# STM_MCU.net
KiCad netlist of a schematic drawn in Altium Designer
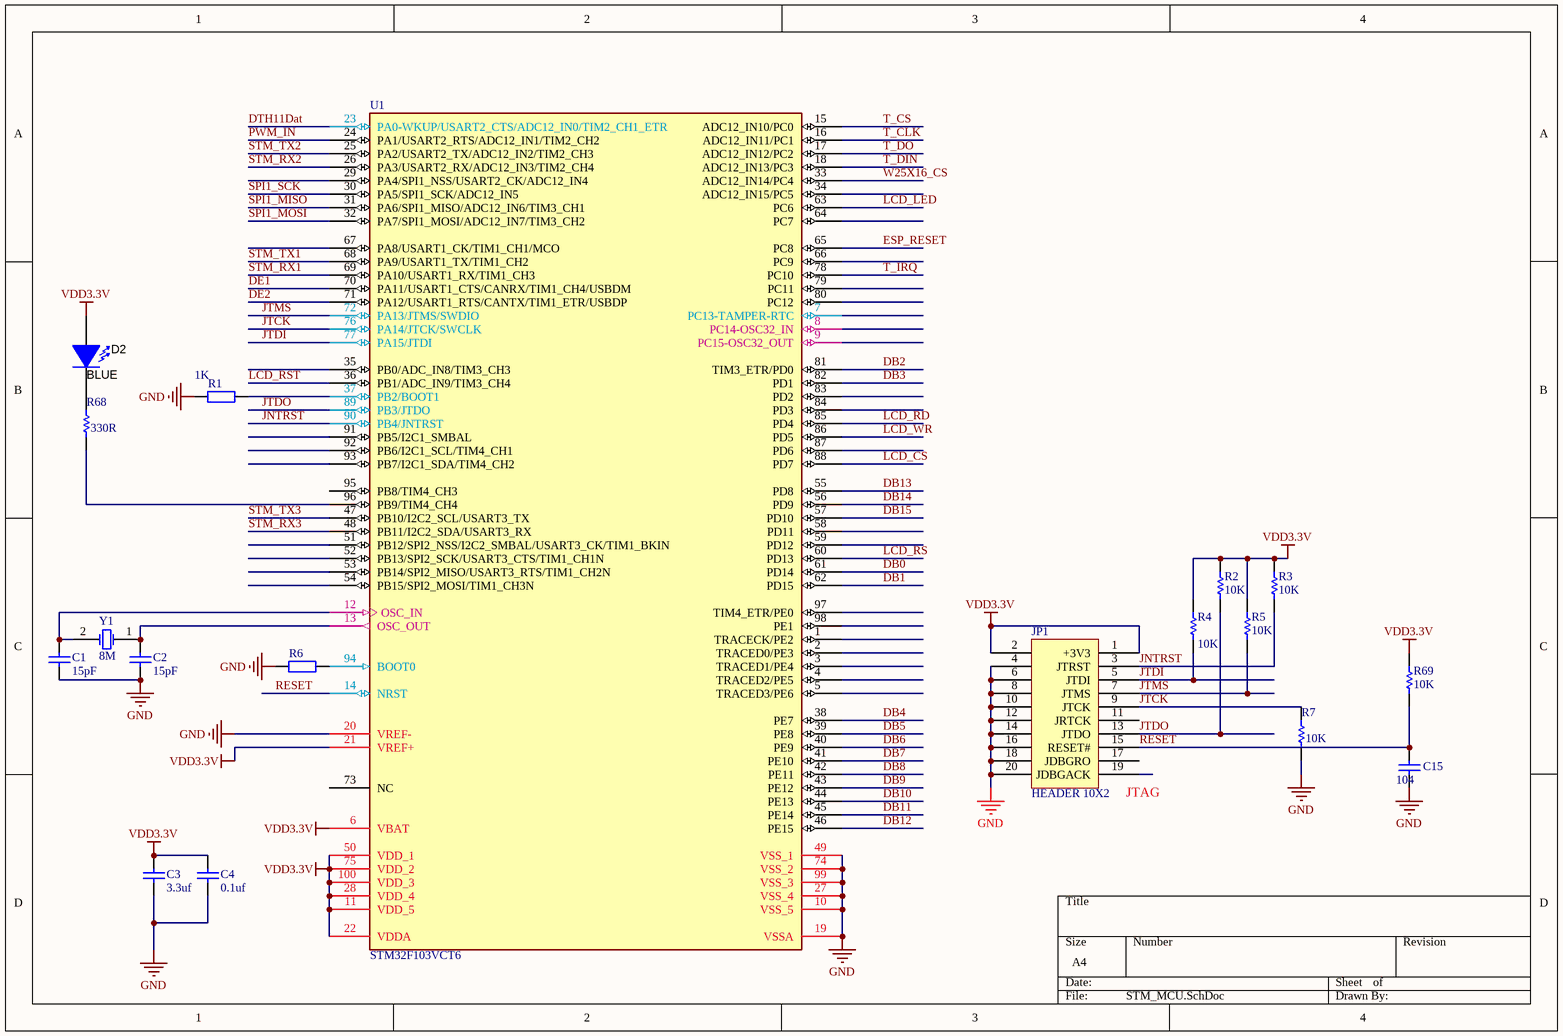
[diagram p0: STM_MCU.SchDoc]

(export (version "E")
  (design (tool "Eeschema 10.0.6"))
  (components
    (comp (ref "C1")
      (value "15pF")
      (footprint "C0805")
      (description "Capacitor")
      (fields (field (name "Comment") "Cap") (field (name "PUBLISHER") "Altium Limited"))
      (libsource (lib "Miscellaneous Devices") (part "Cap"))
    )
    (comp (ref "C2")
      (value "15pF")
      (footprint "C0805")
      (description "Capacitor")
      (fields (field (name "Comment") "Cap") (field (name "PUBLISHER") "Altium Limited"))
      (libsource (lib "Miscellaneous Devices") (part "Cap"))
    )
    (comp (ref "C3")
      (value "3.3uf")
      (footprint "C0805")
      (description "Capacitor")
      (fields
        (field (name "MANUFACTURER") "Generic Components")
        (field (name "Comment") "Cap")
        (field (name "PUBLISHER") "Altium Hobart Technology Centre")
      )
      (libsource (lib "Miscellaneous Devices") (part "Cap"))
    )
    (comp (ref "C4")
      (value "0.1uf")
      (footprint "C0805")
      (description "Capacitor")
      (fields
        (field (name "MANUFACTURER") "Generic Components")
        (field (name "Comment") "Cap")
        (field (name "PUBLISHER") "Altium Hobart Technology Centre")
      )
      (libsource (lib "Miscellaneous Devices") (part "Cap"))
    )
    (comp (ref "C15")
      (value "104")
      (footprint "C0805")
      (description "Capacitor")
      (fields (field (name "PUBLISHER") "Altium Limited"))
      (libsource (lib "main board") (part "Cap_2"))
    )
    (comp (ref "D2")
      (value "BLUE")
      (footprint "D0805")
      (description "LED, GREEN SMD")
      (fields
        (field (name "MANUFACTURER") "Rohm")
        (field (name "PARTNUMBER") "SML-P12YTT86")
        (field (name "PUBLISHER") "Texas Instruments")
      )
      (libsource (lib "REl") (part "SML-P12YTT86"))
    )
    (comp (ref "JP1")
      (value "HEADER 10X2")
      (footprint "STM32-JLINK")
      (libsource (lib "*") (part "HEADER 10X2"))
    )
    (comp (ref "R1")
      (value "1K")
      (footprint "0805")
      (fields (field (name "Comment") "Res2"))
      (libsource (lib "S1") (part "RES"))
    )
    (comp (ref "R2")
      (value "10K")
      (footprint "0805")
      (description "Semiconductor Resistor")
      (fields (field (name "Comment") "Res Semi") (field (name "PUBLISHER") "Altium Limited"))
      (libsource (lib "Miscellaneous Devices") (part "Res Semi"))
    )
    (comp (ref "R3")
      (value "10K")
      (footprint "0805")
      (description "Semiconductor Resistor")
      (fields (field (name "Comment") "Res Semi") (field (name "PUBLISHER") "Altium Limited"))
      (libsource (lib "Miscellaneous Devices") (part "Res Semi"))
    )
    (comp (ref "R4")
      (value "10K")
      (footprint "0805")
      (description "Semiconductor Resistor")
      (fields (field (name "Comment") "Res Semi") (field (name "PUBLISHER") "Altium Limited"))
      (libsource (lib "Miscellaneous Devices") (part "Res Semi"))
    )
    (comp (ref "R5")
      (value "10K")
      (footprint "0805")
      (description "Semiconductor Resistor")
      (fields (field (name "Comment") "Res Semi") (field (name "PUBLISHER") "Altium Limited"))
      (libsource (lib "Miscellaneous Devices") (part "Res Semi"))
    )
    (comp (ref "R6") (value "Res2") (footprint "0805") (libsource (lib "S1") (part "RES")))
    (comp (ref "R7")
      (value "10K")
      (footprint "0805")
      (description "Semiconductor Resistor")
      (fields (field (name "Comment") "Res Semi") (field (name "PUBLISHER") "Altium Limited"))
      (libsource (lib "Miscellaneous Devices") (part "Res Semi"))
    )
    (comp (ref "R68")
      (value "330R")
      (footprint "0805")
      (description "Semiconductor Resistor")
      (fields (field (name "Comment") "Res Semi") (field (name "PUBLISHER") "Altium Limited"))
      (libsource (lib "Miscellaneous Devices") (part "Res Semi"))
    )
    (comp (ref "R69")
      (value "10K")
      (footprint "0805")
      (description "Semiconductor Resistor")
      (fields (field (name "PUBLISHER") "Altium Limited"))
      (libsource (lib "Miscellaneous Devices") (part "Res Semi"))
    )
    (comp (ref "U1")
      (value "STM32F103VCT6")
      (footprint "LQFP100_M")
      (description "STM32 ARM-based 32-bit MCU with 64 Kbytes Flash, 100-pin LQFP, Industrial Temperature")
      (fields (field (name "PUBLISHER") "*"))
      (libsource (lib "Microcontroller Unit") (part "STM32F103VBT6"))
    )
    (comp (ref "Y1")
      (value "XTAL")
      (footprint "CY")
      (description "Crystal Oscillator")
      (fields (field (name "ALTIUM_UNNAMED_1") "8M") (field (name "PUBLISHER") "Altium Limited"))
      (libsource (lib "Miscellaneous Devices") (part "XTAL"))
    )
  )
  (nets
    (net (code "1") (name "/DB0") (class "Default")
      (node (ref "U1") (pin "61") (pinfunction "PD14_61") (pintype "bidirectional"))
    )
    (net (code "2") (name "/DB1") (class "Default")
      (node (ref "U1") (pin "62") (pinfunction "PD15_62") (pintype "bidirectional"))
    )
    (net (code "3") (name "/DB2") (class "Default")
      (node (ref "U1") (pin "81") (pinfunction "TIM3_ETR/PD0_81") (pintype "bidirectional"))
    )
    (net (code "4") (name "/DB3") (class "Default")
      (node (ref "U1") (pin "82") (pinfunction "PD1_82") (pintype "bidirectional"))
    )
    (net (code "5") (name "/DB4") (class "Default")
      (node (ref "U1") (pin "38") (pinfunction "PE7_38") (pintype "bidirectional"))
    )
    (net (code "6") (name "/DB5") (class "Default")
      (node (ref "U1") (pin "39") (pinfunction "PE8_39") (pintype "bidirectional"))
    )
    (net (code "7") (name "/DB6") (class "Default")
      (node (ref "U1") (pin "40") (pinfunction "PE9_40") (pintype "bidirectional"))
    )
    (net (code "8") (name "/DB7") (class "Default")
      (node (ref "U1") (pin "41") (pinfunction "PE10_41") (pintype "bidirectional"))
    )
    (net (code "9") (name "/DB8") (class "Default")
      (node (ref "U1") (pin "42") (pinfunction "PE11_42") (pintype "bidirectional"))
    )
    (net (code "10") (name "/DB9") (class "Default")
      (node (ref "U1") (pin "43") (pinfunction "PE12_43") (pintype "bidirectional"))
    )
    (net (code "11") (name "/DB10") (class "Default")
      (node (ref "U1") (pin "44") (pinfunction "PE13_44") (pintype "bidirectional"))
    )
    (net (code "12") (name "/DB11") (class "Default")
      (node (ref "U1") (pin "45") (pinfunction "PE14_45") (pintype "bidirectional"))
    )
    (net (code "13") (name "/DB12") (class "Default")
      (node (ref "U1") (pin "46") (pinfunction "PE15_46") (pintype "bidirectional"))
    )
    (net (code "14") (name "/DB13") (class "Default")
      (node (ref "U1") (pin "55") (pinfunction "PD8_55") (pintype "bidirectional"))
    )
    (net (code "15") (name "/DB14") (class "Default")
      (node (ref "U1") (pin "56") (pinfunction "PD9_56") (pintype "bidirectional"))
    )
    (net (code "16") (name "/DB15") (class "Default")
      (node (ref "U1") (pin "57") (pinfunction "PD10_57") (pintype "bidirectional"))
    )
    (net (code "17") (name "/DE1") (class "Default")
      (node (ref "U1") (pin "70") (pinfunction "PA11/USART1_CTS/CANRX/TIM1_CH4/USBDM_70") (pintype "bidirectional"))
    )
    (net (code "18") (name "/DE2") (class "Default")
      (node (ref "U1") (pin "71") (pinfunction "PA12/USART1_RTS/CANTX/TIM1_ETR/USBDP_71") (pintype "bidirectional"))
    )
    (net (code "19") (name "/DTH11Dat") (class "Default")
      (node (ref "U1") (pin "23") (pinfunction "PA0-WKUP/USART2_CTS/ADC12_IN0/TIM2_CH1_ETR_23") (pintype "bidirectional"))
    )
    (net (code "20") (name "/ESP_RESET") (class "Default")
      (node (ref "U1") (pin "65") (pinfunction "PC8_65") (pintype "bidirectional"))
    )
    (net (code "21") (name "/JNTRST") (class "Default")
      (node (ref "JP1") (pin "3") (pinfunction "JTRST_3") (pintype "passive"))
      (node (ref "R3") (pin "1") (pinfunction "1_1") (pintype "passive"))
      (node (ref "U1") (pin "90") (pinfunction "PB4/JNTRST_90") (pintype "bidirectional"))
    )
    (net (code "22") (name "/JTCK") (class "Default")
      (node (ref "JP1") (pin "9") (pinfunction "JTCK_9") (pintype "passive"))
      (node (ref "R7") (pin "2") (pinfunction "2_2") (pintype "passive"))
      (node (ref "U1") (pin "76") (pinfunction "PA14/JTCK/SWCLK_76") (pintype "bidirectional"))
    )
    (net (code "23") (name "/JTDI") (class "Default")
      (node (ref "JP1") (pin "5") (pinfunction "JTDI_5") (pintype "passive"))
      (node (ref "R4") (pin "1") (pinfunction "1_1") (pintype "passive"))
      (node (ref "U1") (pin "77") (pinfunction "PA15/JTDI_77") (pintype "bidirectional"))
    )
    (net (code "24") (name "/JTDO") (class "Default")
      (node (ref "JP1") (pin "13") (pinfunction "JTDO_13") (pintype "passive"))
      (node (ref "R2") (pin "1") (pinfunction "1_1") (pintype "passive"))
      (node (ref "U1") (pin "89") (pinfunction "PB3/JTDO_89") (pintype "bidirectional"))
    )
    (net (code "25") (name "/JTMS") (class "Default")
      (node (ref "JP1") (pin "7") (pinfunction "JTMS_7") (pintype "passive"))
      (node (ref "R5") (pin "1") (pinfunction "1_1") (pintype "passive"))
      (node (ref "U1") (pin "72") (pinfunction "PA13/JTMS/SWDIO_72") (pintype "bidirectional"))
    )
    (net (code "26") (name "/LCD_CS") (class "Default")
      (node (ref "U1") (pin "88") (pinfunction "PD7_88") (pintype "bidirectional"))
    )
    (net (code "27") (name "/LCD_LED") (class "Default")
      (node (ref "U1") (pin "63") (pinfunction "PC6_63") (pintype "bidirectional"))
    )
    (net (code "28") (name "/LCD_RD") (class "Default")
      (node (ref "U1") (pin "85") (pinfunction "PD4_85") (pintype "bidirectional"))
    )
    (net (code "29") (name "/LCD_RS") (class "Default")
      (node (ref "U1") (pin "60") (pinfunction "PD13_60") (pintype "bidirectional"))
    )
    (net (code "30") (name "/LCD_RST") (class "Default")
      (node (ref "U1") (pin "36") (pinfunction "PB1/ADC_IN9/TIM3_CH4_36") (pintype "bidirectional"))
    )
    (net (code "31") (name "/LCD_WR") (class "Default")
      (node (ref "U1") (pin "86") (pinfunction "PD5_86") (pintype "bidirectional"))
    )
    (net (code "32") (name "/PWM_IN") (class "Default")
      (node (ref "U1") (pin "24") (pinfunction "PA1/USART2_RTS/ADC12_IN1/TIM2_CH2_24") (pintype "bidirectional"))
    )
    (net (code "33") (name "/RESET") (class "Default")
      (node (ref "C15") (pin "2") (pinfunction "2_2") (pintype "passive"))
      (node (ref "JP1") (pin "15") (pinfunction "RESET#_15") (pintype "passive"))
      (node (ref "R69") (pin "1") (pinfunction "1_1") (pintype "passive"))
      (node (ref "U1") (pin "14") (pinfunction "NRST_14") (pintype "bidirectional"))
    )
    (net (code "34") (name "/SPI1_MISO") (class "Default")
      (node (ref "U1") (pin "31") (pinfunction "PA6/SPI1_MISO/ADC12_IN6/TIM3_CH1_31") (pintype "bidirectional"))
    )
    (net (code "35") (name "/SPI1_MOSI") (class "Default")
      (node (ref "U1") (pin "32") (pinfunction "PA7/SPI1_MOSI/ADC12_IN7/TIM3_CH2_32") (pintype "bidirectional"))
    )
    (net (code "36") (name "/SPI1_SCK") (class "Default")
      (node (ref "U1") (pin "30") (pinfunction "PA5/SPI1_SCK/ADC12_IN5_30") (pintype "bidirectional"))
    )
    (net (code "37") (name "/STM_RX1") (class "Default")
      (node (ref "U1") (pin "69") (pinfunction "PA10/USART1_RX/TIM1_CH3_69") (pintype "bidirectional"))
    )
    (net (code "38") (name "/STM_RX2") (class "Default")
      (node (ref "U1") (pin "26") (pinfunction "PA3/USART2_RX/ADC12_IN3/TIM2_CH4_26") (pintype "bidirectional"))
    )
    (net (code "39") (name "/STM_RX3") (class "Default")
      (node (ref "U1") (pin "48") (pinfunction "PB11/I2C2_SDA/USART3_RX_48") (pintype "bidirectional"))
    )
    (net (code "40") (name "/STM_TX1") (class "Default")
      (node (ref "U1") (pin "68") (pinfunction "PA9/USART1_TX/TIM1_CH2_68") (pintype "bidirectional"))
    )
    (net (code "41") (name "/STM_TX2") (class "Default")
      (node (ref "U1") (pin "25") (pinfunction "PA2/USART2_TX/ADC12_IN2/TIM2_CH3_25") (pintype "bidirectional"))
    )
    (net (code "42") (name "/STM_TX3") (class "Default")
      (node (ref "U1") (pin "47") (pinfunction "PB10/I2C2_SCL/USART3_TX_47") (pintype "bidirectional"))
    )
    (net (code "43") (name "/T_CLK") (class "Default")
      (node (ref "U1") (pin "16") (pinfunction "ADC12_IN11/PC1_16") (pintype "bidirectional"))
    )
    (net (code "44") (name "/T_CS") (class "Default")
      (node (ref "U1") (pin "15") (pinfunction "ADC12_IN10/PC0_15") (pintype "bidirectional"))
    )
    (net (code "45") (name "/T_DIN") (class "Default")
      (node (ref "U1") (pin "18") (pinfunction "ADC12_IN13/PC3_18") (pintype "bidirectional"))
    )
    (net (code "46") (name "/T_DO") (class "Default")
      (node (ref "U1") (pin "17") (pinfunction "ADC12_IN12/PC2_17") (pintype "bidirectional"))
    )
    (net (code "47") (name "/T_IRQ") (class "Default")
      (node (ref "U1") (pin "78") (pinfunction "PC10_78") (pintype "bidirectional"))
    )
    (net (code "48") (name "/W25X16_CS") (class "Default")
      (node (ref "U1") (pin "33") (pinfunction "ADC12_IN14/PC4_33") (pintype "bidirectional"))
    )
    (net (code "49") (name "GND") (class "Default")
      (node (ref "C1") (pin "1") (pinfunction "1_1") (pintype "passive"))
      (node (ref "C15") (pin "1") (pinfunction "1_1") (pintype "passive"))
      (node (ref "C2") (pin "1") (pinfunction "1_1") (pintype "passive"))
      (node (ref "C3") (pin "2") (pinfunction "2_2") (pintype "passive"))
      (node (ref "C4") (pin "2") (pinfunction "2_2") (pintype "passive"))
      (node (ref "JP1") (pin "10") (pintype "passive"))
      (node (ref "JP1") (pin "12") (pintype "passive"))
      (node (ref "JP1") (pin "14") (pintype "passive"))
      (node (ref "JP1") (pin "16") (pintype "passive"))
      (node (ref "JP1") (pin "18") (pintype "passive"))
      (node (ref "JP1") (pin "20") (pintype "passive"))
      (node (ref "JP1") (pin "4") (pintype "passive"))
      (node (ref "JP1") (pin "6") (pintype "passive"))
      (node (ref "JP1") (pin "8") (pintype "passive"))
      (node (ref "R1") (pin "1") (pinfunction "1_1") (pintype "passive"))
      (node (ref "R6") (pin "1") (pinfunction "1_1") (pintype "passive"))
      (node (ref "R7") (pin "1") (pinfunction "1_1") (pintype "passive"))
      (node (ref "U1") (pin "10") (pinfunction "VSS_5_10") (pintype "power_in"))
      (node (ref "U1") (pin "19") (pinfunction "VSSA_19") (pintype "power_in"))
      (node (ref "U1") (pin "20") (pinfunction "VREF-_20") (pintype "power_in"))
      (node (ref "U1") (pin "27") (pinfunction "VSS_4_27") (pintype "power_in"))
      (node (ref "U1") (pin "49") (pinfunction "VSS_1_49") (pintype "power_in"))
      (node (ref "U1") (pin "74") (pinfunction "VSS_2_74") (pintype "power_in"))
      (node (ref "U1") (pin "99") (pinfunction "VSS_3_99") (pintype "power_in"))
    )
    (net (code "50") (name "Net-(D2-K)") (class "Default")
      (node (ref "D2") (pin "2") (pinfunction "K_2") (pintype "passive"))
      (node (ref "R68") (pin "2") (pinfunction "2_2") (pintype "passive"))
    )
    (net (code "51") (name "Net-(U1-BOOT0)") (class "Default")
      (node (ref "R6") (pin "2") (pinfunction "2_2") (pintype "passive"))
      (node (ref "U1") (pin "94") (pinfunction "BOOT0_94") (pintype "input"))
    )
    (net (code "52") (name "Net-(U1-OSC_IN)") (class "Default")
      (node (ref "C1") (pin "2") (pinfunction "2_2") (pintype "passive"))
      (node (ref "U1") (pin "12") (pinfunction "OSC_IN_12") (pintype "input"))
      (node (ref "Y1") (pin "2") (pinfunction "OSC2_2") (pintype "passive"))
    )
    (net (code "53") (name "Net-(U1-OSC_OUT)") (class "Default")
      (node (ref "C2") (pin "2") (pinfunction "2_2") (pintype "passive"))
      (node (ref "U1") (pin "13") (pinfunction "OSC_OUT_13") (pintype "output"))
      (node (ref "Y1") (pin "1") (pinfunction "OSC1_1") (pintype "passive"))
    )
    (net (code "54") (name "Net-(U1-PB2{slash}BOOT1)") (class "Default")
      (node (ref "R1") (pin "2") (pinfunction "2_2") (pintype "passive"))
      (node (ref "U1") (pin "37") (pinfunction "PB2/BOOT1_37") (pintype "bidirectional"))
    )
    (net (code "55") (name "Net-(U1-PB9{slash}TIM4_CH4)") (class "Default")
      (node (ref "R68") (pin "1") (pinfunction "1_1") (pintype "passive"))
      (node (ref "U1") (pin "96") (pinfunction "PB9/TIM4_CH4_96") (pintype "bidirectional"))
    )
    (net (code "56") (name "VDD3.3V") (class "Default")
      (node (ref "C3") (pin "1") (pinfunction "1_1") (pintype "passive"))
      (node (ref "C4") (pin "1") (pinfunction "1_1") (pintype "passive"))
      (node (ref "D2") (pin "1") (pinfunction "A_1") (pintype "passive"))
      (node (ref "JP1") (pin "1") (pinfunction "+3V3_1") (pintype "passive"))
      (node (ref "JP1") (pin "2") (pintype "passive"))
      (node (ref "R2") (pin "2") (pinfunction "2_2") (pintype "passive"))
      (node (ref "R3") (pin "2") (pinfunction "2_2") (pintype "passive"))
      (node (ref "R4") (pin "2") (pinfunction "2_2") (pintype "passive"))
      (node (ref "R5") (pin "2") (pinfunction "2_2") (pintype "passive"))
      (node (ref "R69") (pin "2") (pinfunction "2_2") (pintype "passive"))
      (node (ref "U1") (pin "100") (pinfunction "VDD_3_100") (pintype "power_in"))
      (node (ref "U1") (pin "11") (pinfunction "VDD_5_11") (pintype "power_in"))
      (node (ref "U1") (pin "21") (pinfunction "VREF+_21") (pintype "power_in"))
      (node (ref "U1") (pin "22") (pinfunction "VDDA_22") (pintype "power_in"))
      (node (ref "U1") (pin "28") (pinfunction "VDD_4_28") (pintype "power_in"))
      (node (ref "U1") (pin "50") (pinfunction "VDD_1_50") (pintype "power_in"))
      (node (ref "U1") (pin "6") (pinfunction "VBAT_6") (pintype "power_in"))
      (node (ref "U1") (pin "75") (pinfunction "VDD_2_75") (pintype "power_in"))
    )
    (net (code "57") (name "unconnected-(JP1-JDBGACK-Pad19)") (class "Default")
      (node (ref "JP1") (pin "19") (pinfunction "JDBGACK_19") (pintype "passive"))
    )
    (net (code "58") (name "unconnected-(JP1-JDBGRO-Pad17)") (class "Default")
      (node (ref "JP1") (pin "17") (pinfunction "JDBGRO_17") (pintype "passive"))
    )
    (net (code "59") (name "unconnected-(JP1-JRTCK-Pad11)") (class "Default")
      (node (ref "JP1") (pin "11") (pinfunction "JRTCK_11") (pintype "passive"))
    )
    (net (code "60") (name "unconnected-(U1-ADC12_IN15{slash}PC5-Pad34)") (class "Default")
      (node (ref "U1") (pin "34") (pinfunction "ADC12_IN15/PC5_34") (pintype "bidirectional"))
    )
    (net (code "61") (name "unconnected-(U1-NC-Pad73)") (class "Default")
      (node (ref "U1") (pin "73") (pinfunction "NC_73") (pintype "tri_state"))
    )
    (net (code "62") (name "unconnected-(U1-PA4{slash}SPI1_NSS{slash}USART2_CK{slash}ADC12_IN4-Pad29)") (class "Default")
      (node (ref "U1") (pin "29") (pinfunction "PA4/SPI1_NSS/USART2_CK/ADC12_IN4_29") (pintype "bidirectional"))
    )
    (net (code "63") (name "unconnected-(U1-PA8{slash}USART1_CK{slash}TIM1_CH1{slash}MCO-Pad67)") (class "Default")
      (node (ref "U1") (pin "67") (pinfunction "PA8/USART1_CK/TIM1_CH1/MCO_67") (pintype "bidirectional"))
    )
    (net (code "64") (name "unconnected-(U1-PB0{slash}ADC_IN8{slash}TIM3_CH3-Pad35)") (class "Default")
      (node (ref "U1") (pin "35") (pinfunction "PB0/ADC_IN8/TIM3_CH3_35") (pintype "bidirectional"))
    )
    (net (code "65") (name "unconnected-(U1-PB5{slash}I2C1_SMBAL-Pad91)") (class "Default")
      (node (ref "U1") (pin "91") (pinfunction "PB5/I2C1_SMBAL_91") (pintype "bidirectional"))
    )
    (net (code "66") (name "unconnected-(U1-PB6{slash}I2C1_SCL{slash}TIM4_CH1-Pad92)") (class "Default")
      (node (ref "U1") (pin "92") (pinfunction "PB6/I2C1_SCL/TIM4_CH1_92") (pintype "bidirectional"))
    )
    (net (code "67") (name "unconnected-(U1-PB7{slash}I2C1_SDA{slash}TIM4_CH2-Pad93)") (class "Default")
      (node (ref "U1") (pin "93") (pinfunction "PB7/I2C1_SDA/TIM4_CH2_93") (pintype "bidirectional"))
    )
    (net (code "68") (name "unconnected-(U1-PB8{slash}TIM4_CH3-Pad95)") (class "Default")
      (node (ref "U1") (pin "95") (pinfunction "PB8/TIM4_CH3_95") (pintype "bidirectional"))
    )
    (net (code "69") (name "unconnected-(U1-PB12{slash}SPI2_NSS{slash}I2C2_SMBAL{slash}USART3_CK{slash}TIM1_BKIN-Pad51)") (class "Default")
      (node (ref "U1") (pin "51") (pinfunction "PB12/SPI2_NSS/I2C2_SMBAL/USART3_CK/TIM1_BKIN_51") (pintype "bidirectional"))
    )
    (net (code "70") (name "unconnected-(U1-PB13{slash}SPI2_SCK{slash}USART3_CTS{slash}TIM1_CH1N-Pad52)") (class "Default")
      (node (ref "U1") (pin "52") (pinfunction "PB13/SPI2_SCK/USART3_CTS/TIM1_CH1N_52") (pintype "bidirectional"))
    )
    (net (code "71") (name "unconnected-(U1-PB14{slash}SPI2_MISO{slash}USART3_RTS{slash}TIM1_CH2N-Pad53)") (class "Default")
      (node (ref "U1") (pin "53") (pinfunction "PB14/SPI2_MISO/USART3_RTS/TIM1_CH2N_53") (pintype "bidirectional"))
    )
    (net (code "72") (name "unconnected-(U1-PB15{slash}SPI2_MOSI{slash}TIM1_CH3N-Pad54)") (class "Default")
      (node (ref "U1") (pin "54") (pinfunction "PB15/SPI2_MOSI/TIM1_CH3N_54") (pintype "bidirectional"))
    )
    (net (code "73") (name "unconnected-(U1-PC7-Pad64)") (class "Default")
      (node (ref "U1") (pin "64") (pinfunction "PC7_64") (pintype "bidirectional"))
    )
    (net (code "74") (name "unconnected-(U1-PC9-Pad66)") (class "Default")
      (node (ref "U1") (pin "66") (pinfunction "PC9_66") (pintype "bidirectional"))
    )
    (net (code "75") (name "unconnected-(U1-PC11-Pad79)") (class "Default")
      (node (ref "U1") (pin "79") (pinfunction "PC11_79") (pintype "bidirectional"))
    )
    (net (code "76") (name "unconnected-(U1-PC12-Pad80)") (class "Default")
      (node (ref "U1") (pin "80") (pinfunction "PC12_80") (pintype "bidirectional"))
    )
    (net (code "77") (name "unconnected-(U1-PC13-TAMPER-RTC-Pad7)") (class "Default")
      (node (ref "U1") (pin "7") (pinfunction "PC13-TAMPER-RTC_7") (pintype "bidirectional"))
    )
    (net (code "78") (name "unconnected-(U1-PC14-OSC32_IN-Pad8)") (class "Default")
      (node (ref "U1") (pin "8") (pinfunction "PC14-OSC32_IN_8") (pintype "bidirectional"))
    )
    (net (code "79") (name "unconnected-(U1-PC15-OSC32_OUT-Pad9)") (class "Default")
      (node (ref "U1") (pin "9") (pinfunction "PC15-OSC32_OUT_9") (pintype "bidirectional"))
    )
    (net (code "80") (name "unconnected-(U1-PD2-Pad83)") (class "Default")
      (node (ref "U1") (pin "83") (pinfunction "PD2_83") (pintype "bidirectional"))
    )
    (net (code "81") (name "unconnected-(U1-PD3-Pad84)") (class "Default")
      (node (ref "U1") (pin "84") (pinfunction "PD3_84") (pintype "bidirectional"))
    )
    (net (code "82") (name "unconnected-(U1-PD6-Pad87)") (class "Default")
      (node (ref "U1") (pin "87") (pinfunction "PD6_87") (pintype "bidirectional"))
    )
    (net (code "83") (name "unconnected-(U1-PD11-Pad58)") (class "Default")
      (node (ref "U1") (pin "58") (pinfunction "PD11_58") (pintype "bidirectional"))
    )
    (net (code "84") (name "unconnected-(U1-PD12-Pad59)") (class "Default")
      (node (ref "U1") (pin "59") (pinfunction "PD12_59") (pintype "bidirectional"))
    )
    (net (code "85") (name "unconnected-(U1-PE1-Pad98)") (class "Default")
      (node (ref "U1") (pin "98") (pinfunction "PE1_98") (pintype "bidirectional"))
    )
    (net (code "86") (name "unconnected-(U1-TIM4_ETR{slash}PE0-Pad97)") (class "Default")
      (node (ref "U1") (pin "97") (pinfunction "TIM4_ETR/PE0_97") (pintype "bidirectional"))
    )
    (net (code "87") (name "unconnected-(U1-TRACECK{slash}PE2-Pad1)") (class "Default")
      (node (ref "U1") (pin "1") (pinfunction "TRACECK/PE2_1") (pintype "bidirectional"))
    )
    (net (code "88") (name "unconnected-(U1-TRACED0{slash}PE3-Pad2)") (class "Default")
      (node (ref "U1") (pin "2") (pinfunction "TRACED0/PE3_2") (pintype "bidirectional"))
    )
    (net (code "89") (name "unconnected-(U1-TRACED1{slash}PE4-Pad3)") (class "Default")
      (node (ref "U1") (pin "3") (pinfunction "TRACED1/PE4_3") (pintype "bidirectional"))
    )
    (net (code "90") (name "unconnected-(U1-TRACED2{slash}PE5-Pad4)") (class "Default")
      (node (ref "U1") (pin "4") (pinfunction "TRACED2/PE5_4") (pintype "bidirectional"))
    )
    (net (code "91") (name "unconnected-(U1-TRACED3{slash}PE6-Pad5)") (class "Default")
      (node (ref "U1") (pin "5") (pinfunction "TRACED3/PE6_5") (pintype "bidirectional"))
    )
  )
)
